# Hardware_v4.net
KiCad netlist of a schematic drawn in EAGLE
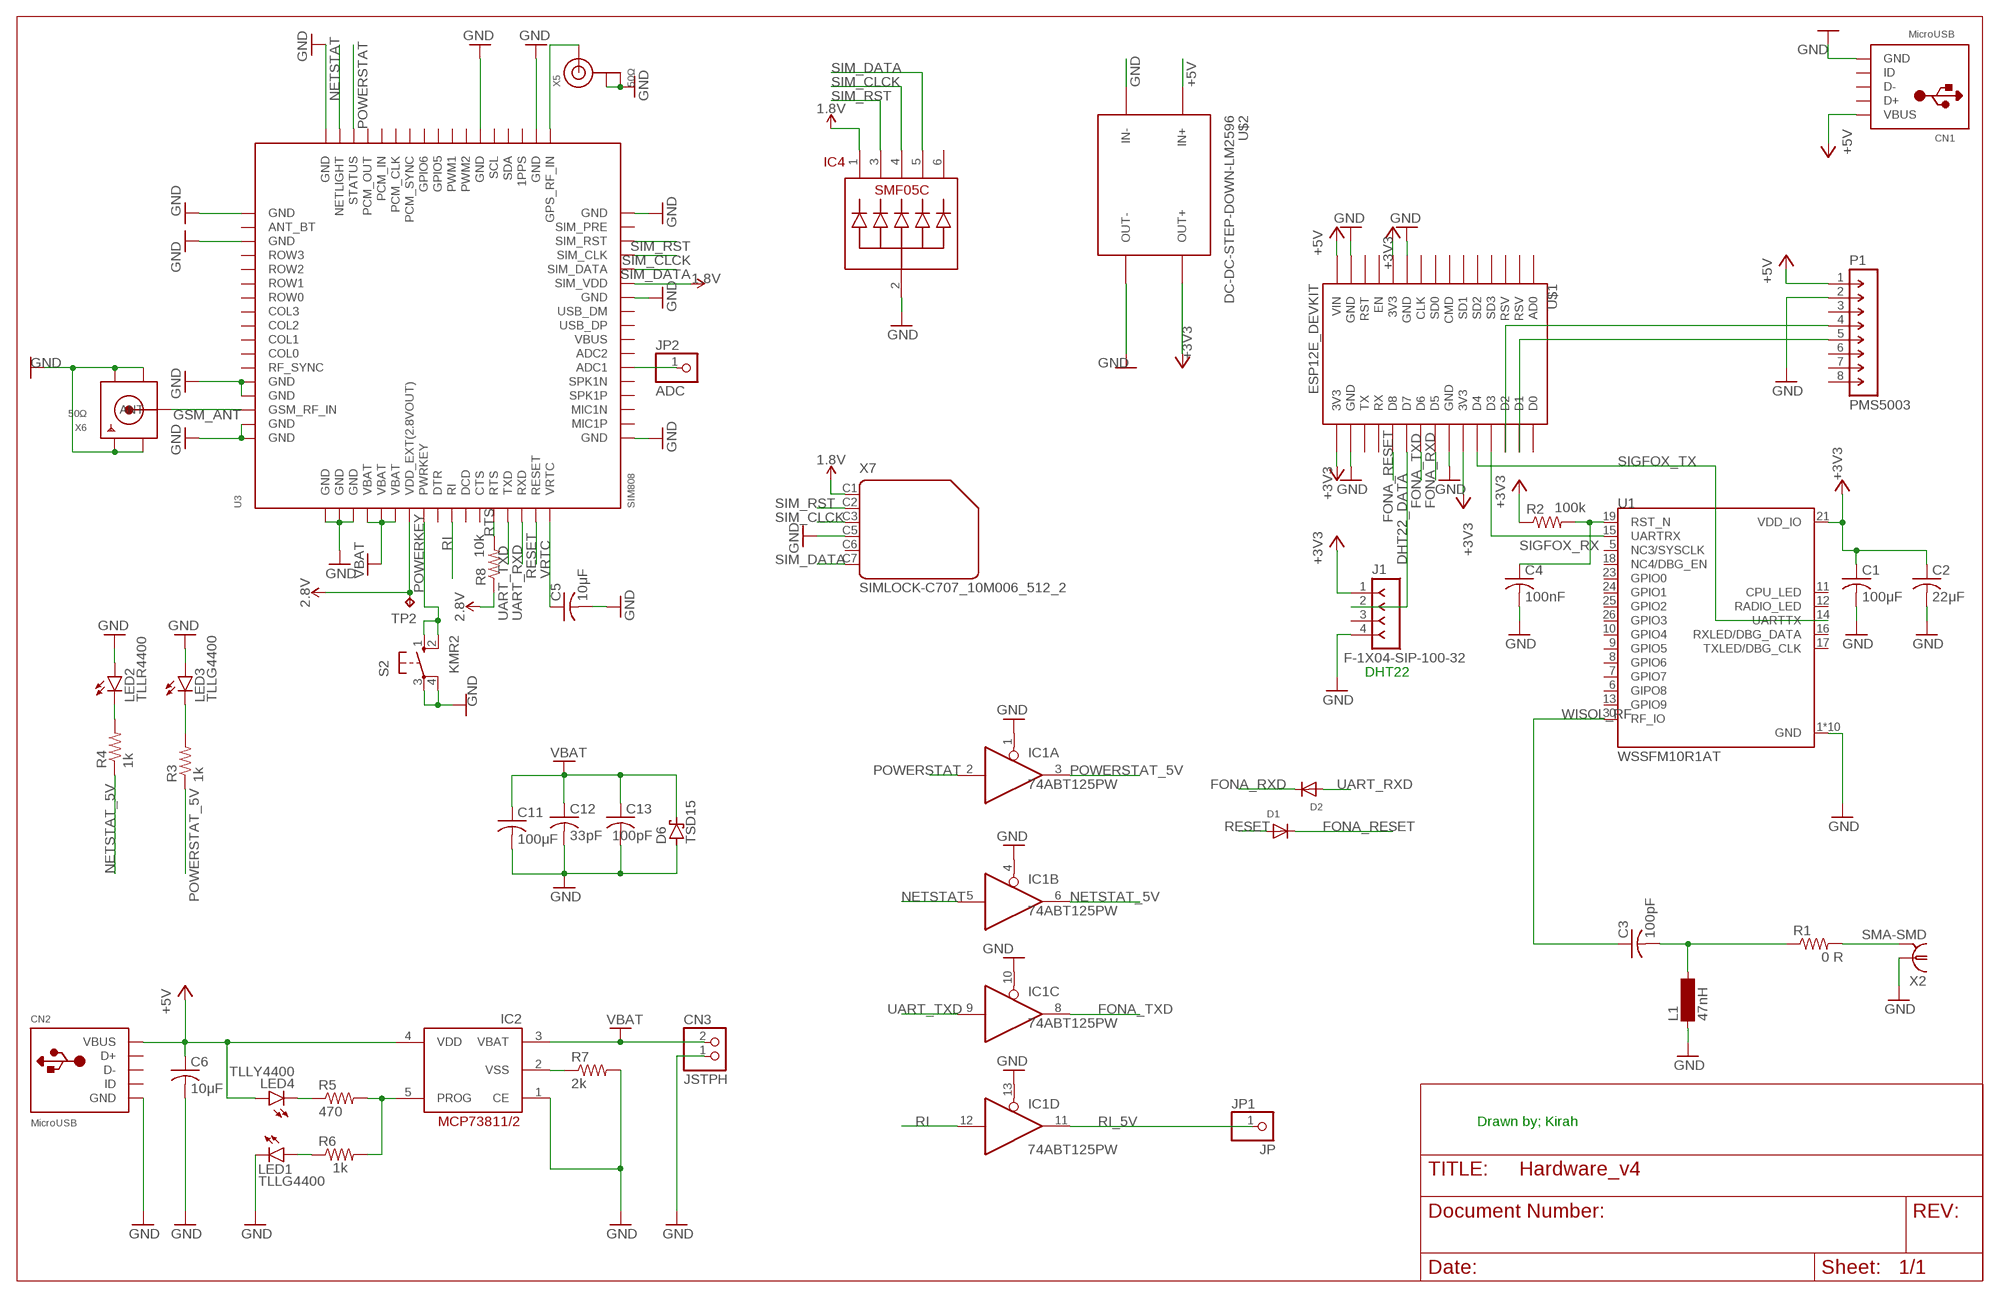
[diagram p0: schematic, sheet 1]

(export (version "E")
  (design (tool "Eeschema 10.0.6"))
  (components
    (comp (ref "C1")
      (value "100μF")
      (footprint "eagle-import:C0201")
      (libsource (lib "eagle-import") (part "rcl_334_C-USC0201"))
    )
    (comp (ref "C2")
      (value "22μF")
      (footprint "eagle-import:C0201")
      (libsource (lib "eagle-import") (part "rcl_334_C-USC0201"))
    )
    (comp (ref "C3")
      (value "100pF")
      (footprint "eagle-import:C0402K")
      (libsource (lib "eagle-import") (part "rcl_334_C-USC0402K"))
    )
    (comp (ref "C4")
      (value "100nF")
      (footprint "eagle-import:C0201")
      (libsource (lib "eagle-import") (part "rcl_334_C-USC0201"))
    )
    (comp (ref "C5")
      (value "10μF")
      (footprint "eagle-import:C0201")
      (libsource (lib "eagle-import") (part "rcl_334_C-USC0201"))
    )
    (comp (ref "C6")
      (value "10μF")
      (footprint "eagle-import:C0201")
      (libsource (lib "eagle-import") (part "rcl_334_C-USC0201"))
    )
    (comp (ref "C11")
      (value "100μF")
      (footprint "eagle-import:C0402")
      (libsource (lib "eagle-import") (part "C-USC0402"))
    )
    (comp (ref "C12")
      (value "33pF")
      (footprint "eagle-import:C0402")
      (libsource (lib "eagle-import") (part "C-USC0402"))
    )
    (comp (ref "C13")
      (value "100pF")
      (footprint "eagle-import:C0402")
      (libsource (lib "eagle-import") (part "C-USC0402"))
    )
    (comp (ref "CN1")
      (value "MicroUSB")
      (footprint "eagle-import:USB-MINIB")
      (libsource (lib "eagle-import") (part "USBMINIB"))
    )
    (comp (ref "CN2")
      (value "MicroUSB")
      (footprint "eagle-import:USB-MINIB")
      (libsource (lib "eagle-import") (part "adafruit@1_USBMINIB"))
    )
    (comp (ref "CN3")
      (value "JSTPH")
      (footprint "eagle-import:JST-PH-2-SMT")
      (libsource (lib "eagle-import") (part "JST_2PIN-SMT"))
    )
    (comp (ref "D1")
      (value "DIODESMA")
      (footprint "eagle-import:SMADIODE")
      (libsource (lib "eagle-import") (part "DIODESMA"))
    )
    (comp (ref "D2")
      (value "DIODESMA")
      (footprint "eagle-import:SMADIODE")
      (libsource (lib "eagle-import") (part "DIODESMA"))
    )
    (comp (ref "D6")
      (value "TSD15")
      (footprint "eagle-import:CB429-15")
      (libsource (lib "eagle-import") (part "TSD15"))
    )
    (comp (ref "IC1")
      (value "74ABT125PW")
      (footprint "eagle-import:TSSOP14")
      (libsource (lib "eagle-import") (part "74125PWABT"))
    )
    (comp (ref "IC2")
      (value "MCP73811/2")
      (footprint "eagle-import:SOT23-5L")
      (libsource (lib "eagle-import") (part "MCP73811/2"))
    )
    (comp (ref "IC4")
      (value "SMF05C")
      (footprint "eagle-import:SC-70-6")
      (libsource (lib "eagle-import") (part "SMF05C"))
    )
    (comp (ref "J1")
      (value "F-1X04-SIP-100-32")
      (footprint "eagle-import:SIP-100-04-32")
      (libsource (lib "eagle-import") (part "F-1X04-SIP-100-32"))
    )
    (comp (ref "JP1")
      (value "JP")
      (footprint "eagle-import:1X01-CLEANBIG")
      (libsource (lib "eagle-import") (part "PINHD-1X1CB"))
    )
    (comp (ref "JP2")
      (value "ADC")
      (footprint "eagle-import:1X01M")
      (libsource (lib "eagle-import") (part "PINHD-1X01_2.00"))
    )
    (comp (ref "L1")
      (value "47nH")
      (footprint "eagle-import:SM-1206")
      (libsource (lib "eagle-import") (part "SM-1206"))
    )
    (comp (ref "LED1")
      (value "TLLG4400")
      (footprint "eagle-import:LED3MM")
      (fields (field (name "MF") "VISHAY SEMICONDUCTOR"))
      (libsource (lib "eagle-import") (part "TLLG4400"))
    )
    (comp (ref "LED2")
      (value "TLLR4400")
      (footprint "eagle-import:LED3MM")
      (fields (field (name "MF") "VISHAY SEMICONDUCTOR"))
      (libsource (lib "eagle-import") (part "TLLR4400"))
    )
    (comp (ref "LED3")
      (value "TLLG4400")
      (footprint "eagle-import:LED3MM")
      (fields (field (name "MF") "VISHAY SEMICONDUCTOR"))
      (libsource (lib "eagle-import") (part "TLLG4400"))
    )
    (comp (ref "LED4")
      (value "TLLY4400")
      (footprint "eagle-import:LED3MM")
      (fields (field (name "MF") "VISHAY SEMICONDUCTOR"))
      (libsource (lib "eagle-import") (part "TLLY4400"))
    )
    (comp (ref "P1")
      (value "PMS5003")
      (footprint "eagle-import:SIP-100-08-40")
      (libsource (lib "eagle-import") (part "M-1X08-SIP-100-40"))
    )
    (comp (ref "R1")
      (value "0 R")
      (footprint "eagle-import:R01005")
      (libsource (lib "eagle-import") (part "R-US_01005"))
    )
    (comp (ref "R2")
      (value "100k")
      (footprint "eagle-import:R0201")
      (libsource (lib "eagle-import") (part "R-US_R0201"))
    )
    (comp (ref "R3")
      (value "1k")
      (footprint "eagle-import:R01005")
      (libsource (lib "eagle-import") (part "R-US_01005"))
    )
    (comp (ref "R4")
      (value "1k")
      (footprint "eagle-import:R01005")
      (libsource (lib "eagle-import") (part "R-US_01005"))
    )
    (comp (ref "R5")
      (value "470")
      (footprint "eagle-import:R01005")
      (libsource (lib "eagle-import") (part "R-US_01005"))
    )
    (comp (ref "R6")
      (value "1k")
      (footprint "eagle-import:R01005")
      (libsource (lib "eagle-import") (part "R-US_01005"))
    )
    (comp (ref "R7")
      (value "2k")
      (footprint "eagle-import:R01005")
      (libsource (lib "eagle-import") (part "R-US_01005"))
    )
    (comp (ref "R8")
      (value "10k")
      (footprint "eagle-import:R01005")
      (libsource (lib "eagle-import") (part "R-US_01005"))
    )
    (comp (ref "S2")
      (value "KMR2")
      (footprint "eagle-import:B3F_40XX")
      (libsource (lib "eagle-import") (part "40/XX"))
    )
    (comp (ref "TP2")
      (value "TPTP10R")
      (footprint "eagle-import:TP10R")
      (libsource (lib "eagle-import") (part "TPTP10R"))
    )
    (comp (ref "U$1")
      (value "ESP12E_DEVKIT")
      (footprint "eagle-import:ESP12E_DEVKIT")
      (libsource (lib "eagle-import") (part "ESP12E_DEVKIT"))
    )
    (comp (ref "U$2")
      (value "DC-DC-STEP-DOWN-LM2596")
      (footprint "eagle-import:DC-DC-STEP-DOWN-LM2596")
      (libsource (lib "eagle-import") (part "DC-DC-STEP-DOWN-LM2596"))
    )
    (comp (ref "U1")
      (value "WSSFM10R1AT")
      (footprint "eagle-import:XCVR_WSSFM10R1AT")
      (fields (field (name "MF") "Avnet Design Services"))
      (libsource (lib "eagle-import") (part "WSSFM10R1AT"))
    )
    (comp (ref "U3")
      (value "SIM808")
      (footprint "eagle-import:SIM900_SMT")
      (libsource (lib "eagle-import") (part "GSM_SIM808_LITERAL"))
    )
    (comp (ref "X2")
      (value "SMA-SMD")
      (footprint "eagle-import:SMA-SMD")
      (libsource (lib "eagle-import") (part "SMA-SMD"))
    )
    (comp (ref "X5")
      (value "50Ω")
      (footprint "eagle-import:U.FL")
      (libsource (lib "eagle-import") (part "ANTENNA_U.FL"))
    )
    (comp (ref "X6")
      (value "50Ω")
      (footprint "eagle-import:SMA_EDGELAUNCH_UFL")
      (libsource (lib "eagle-import") (part "SMACONNECTOR_EDGE_UFL"))
    )
    (comp (ref "X7")
      (value "SIMLOCK-C707_10M006_512_2")
      (footprint "eagle-import:C707_10M006_512_2")
      (libsource (lib "eagle-import") (part "SIMLOCK-C707_10M006_512_2"))
    )
  )
  (nets
    (net (code "1") (name "+3V3") (class "Default")
      (node (ref "C1") (pin "1") (pinfunction "1_1") (pintype "passive"))
      (node (ref "C2") (pin "1") (pinfunction "1_1") (pintype "passive"))
      (node (ref "J1") (pin "1") (pinfunction "1_1") (pintype "passive"))
      (node (ref "R2") (pin "1") (pinfunction "1_1") (pintype "passive"))
      (node (ref "U$1") (pin "3V3@0") (pinfunction "3V3_3V3@0") (pintype "bidirectional"))
      (node (ref "U$1") (pin "3V3@1") (pinfunction "3V3_3V3@1") (pintype "bidirectional"))
      (node (ref "U$1") (pin "3V3@2") (pinfunction "3V3_3V3@2") (pintype "bidirectional"))
      (node (ref "U$2") (pin "OUT+") (pinfunction "OUT+_OUT+") (pintype "bidirectional"))
      (node (ref "U1") (pin "21") (pinfunction "VDD_IO_21") (pintype "power_in"))
    )
    (net (code "2") (name "+5V") (class "Default")
      (node (ref "C6") (pin "1") (pinfunction "1_1") (pintype "passive"))
      (node (ref "CN1") (pin "VBUS") (pinfunction "VBUS_VBUS") (pintype "power_in"))
      (node (ref "CN2") (pin "VBUS") (pinfunction "VBUS_VBUS") (pintype "power_in"))
      (node (ref "IC2") (pin "4") (pinfunction "VDD_4") (pintype "power_in"))
      (node (ref "LED4") (pin "A") (pinfunction "A_A") (pintype "passive"))
      (node (ref "P1") (pin "1") (pinfunction "1_1") (pintype "passive"))
      (node (ref "U$1") (pin "VIN") (pinfunction "VIN_VIN") (pintype "bidirectional"))
      (node (ref "U$2") (pin "IN+") (pinfunction "IN+_IN+") (pintype "bidirectional"))
    )
    (net (code "3") (name "/DHT22_DATA") (class "Default")
      (node (ref "J1") (pin "2") (pinfunction "2_2") (pintype "passive"))
      (node (ref "U$1") (pin "D7") (pinfunction "D7_D7") (pintype "bidirectional"))
    )
    (net (code "4") (name "/FONA_RESET") (class "Default")
      (node (ref "D1") (pin "C") (pinfunction "C_C") (pintype "passive"))
      (node (ref "U$1") (pin "D8") (pinfunction "D8_D8") (pintype "bidirectional"))
    )
    (net (code "5") (name "/FONA_RXD") (class "Default")
      (node (ref "D2") (pin "C") (pinfunction "C_C") (pintype "passive"))
      (node (ref "U$1") (pin "D5") (pinfunction "D5_D5") (pintype "bidirectional"))
    )
    (net (code "6") (name "/FONA_TXD") (class "Default")
      (node (ref "IC1") (pin "8") (pinfunction "O_8") (pintype "tri_state"))
      (node (ref "U$1") (pin "D6") (pinfunction "D6_D6") (pintype "bidirectional"))
    )
    (net (code "7") (name "/GSM_ANT") (class "Default")
      (node (ref "U3") (pin "P$66") (pinfunction "GSM_RF_IN_P$66") (pintype "input"))
      (node (ref "X6") (pin "P") (pinfunction "ANT_P") (pintype "bidirectional"))
    )
    (net (code "8") (name "/NETSTAT") (class "Default")
      (node (ref "IC1") (pin "5") (pinfunction "I_5") (pintype "input"))
      (node (ref "U3") (pin "P$50") (pinfunction "NETLIGHT_P$50") (pintype "output"))
    )
    (net (code "9") (name "/NETSTAT_5V") (class "Default")
      (node (ref "IC1") (pin "6") (pinfunction "O_6") (pintype "tri_state"))
      (node (ref "R4") (pin "1") (pinfunction "1_1") (pintype "passive"))
    )
    (net (code "10") (name "/POWERKEY") (class "Default")
      (node (ref "S2") (pin "1") (pinfunction "S_1") (pintype "passive"))
      (node (ref "S2") (pin "2") (pinfunction "S1_2") (pintype "passive"))
      (node (ref "U3") (pin "P$8") (pinfunction "PWRKEY_P$8") (pintype "input"))
    )
    (net (code "11") (name "/POWERSTAT") (class "Default")
      (node (ref "IC1") (pin "2") (pinfunction "I_2") (pintype "input"))
      (node (ref "U3") (pin "P$49") (pinfunction "STATUS_P$49") (pintype "output"))
    )
    (net (code "12") (name "/POWERSTAT_5V") (class "Default")
      (node (ref "IC1") (pin "3") (pinfunction "O_3") (pintype "tri_state"))
      (node (ref "R3") (pin "1") (pinfunction "1_1") (pintype "passive"))
    )
    (net (code "13") (name "/RESET") (class "Default")
      (node (ref "D1") (pin "A") (pinfunction "A_A") (pintype "passive"))
      (node (ref "U3") (pin "P$16") (pinfunction "RESET_P$16") (pintype "input"))
    )
    (net (code "14") (name "/RI") (class "Default")
      (node (ref "IC1") (pin "12") (pinfunction "I_12") (pintype "input"))
      (node (ref "U3") (pin "P$10") (pinfunction "RI_P$10") (pintype "output"))
    )
    (net (code "15") (name "/RI_5V") (class "Default")
      (node (ref "IC1") (pin "11") (pinfunction "O_11") (pintype "tri_state"))
      (node (ref "JP1") (pin "1") (pinfunction "1_1") (pintype "passive"))
    )
    (net (code "16") (name "/RTS") (class "Default")
      (node (ref "R8") (pin "2") (pinfunction "2_2") (pintype "passive"))
      (node (ref "U3") (pin "P$13") (pinfunction "RTS_P$13") (pintype "input"))
    )
    (net (code "17") (name "/SIGFOX_RX") (class "Default")
      (node (ref "U$1") (pin "D3") (pinfunction "D3_D3") (pintype "bidirectional"))
      (node (ref "U1") (pin "15") (pinfunction "UARTRX_15") (pintype "input"))
    )
    (net (code "18") (name "/SIGFOX_TX") (class "Default")
      (node (ref "U$1") (pin "D4") (pinfunction "D4_D4") (pintype "bidirectional"))
      (node (ref "U1") (pin "14") (pinfunction "UARTTX_14") (pintype "output"))
    )
    (net (code "19") (name "/SIM_CLCK") (class "Default")
      (node (ref "IC4") (pin "4") (pinfunction "4_4") (pintype "bidirectional"))
      (node (ref "U3") (pin "P$31") (pinfunction "SIM_CLK_P$31") (pintype "output"))
      (node (ref "X7") (pin "C3") (pinfunction "3_C3") (pintype "passive"))
    )
    (net (code "20") (name "/SIM_DATA") (class "Default")
      (node (ref "IC4") (pin "5") (pinfunction "5_5") (pintype "bidirectional"))
      (node (ref "U3") (pin "P$30") (pinfunction "SIM_DATA_P$30") (pintype "bidirectional"))
      (node (ref "X7") (pin "C7") (pinfunction "6_C7") (pintype "passive"))
    )
    (net (code "21") (name "/SIM_RST") (class "Default")
      (node (ref "IC4") (pin "3") (pinfunction "3_3") (pintype "bidirectional"))
      (node (ref "U3") (pin "P$32") (pinfunction "SIM_RST_P$32") (pintype "output"))
      (node (ref "X7") (pin "C2") (pinfunction "2_C2") (pintype "passive"))
    )
    (net (code "22") (name "/UART_RXD") (class "Default")
      (node (ref "D2") (pin "A") (pinfunction "A_A") (pintype "passive"))
      (node (ref "U3") (pin "P$15") (pinfunction "RXD_P$15") (pintype "input"))
    )
    (net (code "23") (name "/UART_TXD") (class "Default")
      (node (ref "IC1") (pin "9") (pinfunction "I_9") (pintype "input"))
      (node (ref "U3") (pin "P$14") (pinfunction "TXD_P$14") (pintype "output"))
    )
    (net (code "24") (name "/VBUS") (class "Default")
      (node (ref "U3") (pin "P$25") (pinfunction "VBUS_P$25") (pintype "power_in"))
    )
    (net (code "25") (name "/VRTC") (class "Default")
      (node (ref "C5") (pin "1") (pinfunction "1_1") (pintype "passive"))
      (node (ref "U3") (pin "P$17") (pinfunction "VRTC_P$17") (pintype "power_in"))
    )
    (net (code "26") (name "/WISOL_RF") (class "Default")
      (node (ref "C3") (pin "1") (pinfunction "1_1") (pintype "passive"))
      (node (ref "U1") (pin "30") (pinfunction "RF_IO_30") (pintype "bidirectional"))
    )
    (net (code "27") (name "1.8V") (class "Default")
      (node (ref "IC4") (pin "1") (pinfunction "1_1") (pintype "bidirectional"))
      (node (ref "U3") (pin "P$29") (pinfunction "SIM_VDD_P$29") (pintype "power_in"))
      (node (ref "X7") (pin "C1") (pinfunction "1_C1") (pintype "passive"))
    )
    (net (code "28") (name "2.8V") (class "Default")
      (node (ref "R8") (pin "1") (pinfunction "1_1") (pintype "passive"))
      (node (ref "TP2") (pin "TP") (pinfunction "TP_TP") (pintype "input"))
      (node (ref "U3") (pin "P$7") (pinfunction "VDD_EXT(2.8VOUT)_P$7") (pintype "power_in"))
    )
    (net (code "29") (name "GND") (class "Default")
      (node (ref "C1") (pin "2") (pinfunction "2_2") (pintype "passive"))
      (node (ref "C11") (pin "2") (pinfunction "2_2") (pintype "passive"))
      (node (ref "C12") (pin "2") (pinfunction "2_2") (pintype "passive"))
      (node (ref "C13") (pin "2") (pinfunction "2_2") (pintype "passive"))
      (node (ref "C2") (pin "2") (pinfunction "2_2") (pintype "passive"))
      (node (ref "C4") (pin "2") (pinfunction "2_2") (pintype "passive"))
      (node (ref "C5") (pin "2") (pinfunction "2_2") (pintype "passive"))
      (node (ref "C6") (pin "2") (pinfunction "2_2") (pintype "passive"))
      (node (ref "CN1") (pin "GND") (pinfunction "GND_GND") (pintype "power_in"))
      (node (ref "CN2") (pin "GND") (pinfunction "GND_GND") (pintype "power_in"))
      (node (ref "CN3") (pin "1") (pinfunction "2_1") (pintype "passive"))
      (node (ref "D6") (pin "A") (pinfunction "A_A") (pintype "passive"))
      (node (ref "IC1") (pin "1") (pinfunction "OE_1") (pintype "input"))
      (node (ref "IC1") (pin "10") (pinfunction "OE_10") (pintype "input"))
      (node (ref "IC1") (pin "13") (pinfunction "OE_13") (pintype "input"))
      (node (ref "IC1") (pin "4") (pinfunction "OE_4") (pintype "input"))
      (node (ref "IC2") (pin "1") (pinfunction "CE_1") (pintype "input"))
      (node (ref "IC4") (pin "2") (pinfunction "2_2") (pintype "bidirectional"))
      (node (ref "J1") (pin "4") (pinfunction "4_4") (pintype "passive"))
      (node (ref "L1") (pin "1") (pinfunction "1_1") (pintype "passive"))
      (node (ref "LED1") (pin "K") (pinfunction "C_K") (pintype "passive"))
      (node (ref "LED2") (pin "A") (pinfunction "A_A") (pintype "passive"))
      (node (ref "LED3") (pin "A") (pinfunction "A_A") (pintype "passive"))
      (node (ref "P1") (pin "2") (pinfunction "2_2") (pintype "passive"))
      (node (ref "R7") (pin "2") (pinfunction "2_2") (pintype "passive"))
      (node (ref "S2") (pin "3") (pinfunction "P_3") (pintype "passive"))
      (node (ref "S2") (pin "4") (pinfunction "P1_4") (pintype "passive"))
      (node (ref "U$1") (pin "GND@0") (pinfunction "GND_GND@0") (pintype "bidirectional"))
      (node (ref "U$1") (pin "GND@1") (pinfunction "GND_GND@1") (pintype "bidirectional"))
      (node (ref "U$1") (pin "GND@2") (pinfunction "GND_GND@2") (pintype "bidirectional"))
      (node (ref "U$1") (pin "GND@3") (pinfunction "GND_GND@3") (pintype "bidirectional"))
      (node (ref "U$2") (pin "IN-") (pinfunction "IN-_IN-") (pintype "bidirectional"))
      (node (ref "U$2") (pin "OUT-") (pinfunction "OUT-_OUT-") (pintype "bidirectional"))
      (node (ref "U1") (pin "1") (pinfunction "GND_1") (pintype "power_in"))
      (node (ref "U1") (pin "2") (pinfunction "GND_2") (pintype "power_in"))
      (node (ref "U1") (pin "20") (pinfunction "GND_20") (pintype "power_in"))
      (node (ref "U1") (pin "22") (pinfunction "GND_22") (pintype "power_in"))
      (node (ref "U1") (pin "27") (pinfunction "GND_27") (pintype "power_in"))
      (node (ref "U1") (pin "28") (pinfunction "GND_28") (pintype "power_in"))
      (node (ref "U1") (pin "29") (pinfunction "GND_29") (pintype "power_in"))
      (node (ref "U1") (pin "3") (pinfunction "GND_3") (pintype "power_in"))
      (node (ref "U1") (pin "31") (pinfunction "GND_31") (pintype "power_in"))
      (node (ref "U1") (pin "4") (pinfunction "GND_4") (pintype "power_in"))
      (node (ref "U3") (pin "P$1") (pinfunction "GND_P$1") (pintype "power_in"))
      (node (ref "U3") (pin "P$18") (pinfunction "GND_P$18") (pintype "power_in"))
      (node (ref "U3") (pin "P$2") (pinfunction "GND_P$2") (pintype "power_in"))
      (node (ref "U3") (pin "P$28") (pinfunction "GND_P$28") (pintype "power_in"))
      (node (ref "U3") (pin "P$3") (pinfunction "GND_P$3") (pintype "power_in"))
      (node (ref "U3") (pin "P$34") (pinfunction "GND_P$34") (pintype "power_in"))
      (node (ref "U3") (pin "P$36") (pinfunction "GND_P$36") (pintype "power_in"))
      (node (ref "U3") (pin "P$40") (pinfunction "GND_P$40") (pintype "power_in"))
      (node (ref "U3") (pin "P$51") (pinfunction "GND_P$51") (pintype "power_in"))
      (node (ref "U3") (pin "P$52") (pinfunction "GND_P$52") (pintype "power_in"))
      (node (ref "U3") (pin "P$54") (pinfunction "GND_P$54") (pintype "power_in"))
      (node (ref "U3") (pin "P$64") (pinfunction "GND_P$64") (pintype "power_in"))
      (node (ref "U3") (pin "P$65") (pinfunction "GND_P$65") (pintype "power_in"))
      (node (ref "U3") (pin "P$67") (pinfunction "GND_P$67") (pintype "power_in"))
      (node (ref "U3") (pin "P$68") (pinfunction "GND_P$68") (pintype "power_in"))
      (node (ref "X2") (pin "1") (pinfunction "1_1") (pintype "passive"))
      (node (ref "X5") (pin "1") (pinfunction "GND_1") (pintype "passive"))
      (node (ref "X5") (pin "2") (pinfunction "GND_2") (pintype "passive"))
      (node (ref "X6") (pin "GND@1") (pinfunction "GND1_GND@1") (pintype "power_in"))
      (node (ref "X6") (pin "GND@2") (pinfunction "GND2_GND@2") (pintype "power_in"))
      (node (ref "X6") (pin "GND@3") (pinfunction "GND3_GND@3") (pintype "power_in"))
      (node (ref "X6") (pin "GND@4") (pinfunction "GND4_GND@4") (pintype "power_in"))
      (node (ref "X7") (pin "C5") (pinfunction "4_C5") (pintype "passive"))
    )
    (net (code "30") (name "Net-(C3-Pad2)") (class "Default")
      (node (ref "C3") (pin "2") (pinfunction "2_2") (pintype "passive"))
      (node (ref "L1") (pin "2") (pinfunction "2_2") (pintype "passive"))
      (node (ref "R1") (pin "1") (pinfunction "1_1") (pintype "passive"))
    )
    (net (code "31") (name "Net-(IC2-PROG)") (class "Default")
      (node (ref "IC2") (pin "5") (pinfunction "PROG_5") (pintype "input"))
      (node (ref "R5") (pin "2") (pinfunction "2_2") (pintype "passive"))
      (node (ref "R6") (pin "2") (pinfunction "2_2") (pintype "passive"))
    )
    (net (code "32") (name "Net-(IC2-VSS)") (class "Default")
      (node (ref "IC2") (pin "2") (pinfunction "VSS_2") (pintype "power_in"))
      (node (ref "R7") (pin "1") (pinfunction "1_1") (pintype "passive"))
    )
    (net (code "33") (name "Net-(LED1-PadA)") (class "Default")
      (node (ref "LED1") (pin "A") (pinfunction "A_A") (pintype "passive"))
      (node (ref "R6") (pin "1") (pinfunction "1_1") (pintype "passive"))
    )
    (net (code "34") (name "Net-(LED2-C)") (class "Default")
      (node (ref "LED2") (pin "K") (pinfunction "C_K") (pintype "passive"))
      (node (ref "R4") (pin "2") (pinfunction "2_2") (pintype "passive"))
    )
    (net (code "35") (name "Net-(LED3-C)") (class "Default")
      (node (ref "LED3") (pin "K") (pinfunction "C_K") (pintype "passive"))
      (node (ref "R3") (pin "2") (pinfunction "2_2") (pintype "passive"))
    )
    (net (code "36") (name "Net-(LED4-C)") (class "Default")
      (node (ref "LED4") (pin "K") (pinfunction "C_K") (pintype "passive"))
      (node (ref "R5") (pin "1") (pinfunction "1_1") (pintype "passive"))
    )
    (net (code "37") (name "Net-(P1-Pad4)") (class "Default")
      (node (ref "P1") (pin "4") (pinfunction "4_4") (pintype "passive"))
      (node (ref "U$1") (pin "D2") (pinfunction "D2_D2") (pintype "bidirectional"))
    )
    (net (code "38") (name "Net-(P1-Pad5)") (class "Default")
      (node (ref "P1") (pin "5") (pinfunction "5_5") (pintype "passive"))
      (node (ref "U$1") (pin "D1") (pinfunction "D1_D1") (pintype "bidirectional"))
    )
    (net (code "39") (name "Net-(R1-Pad2)") (class "Default")
      (node (ref "R1") (pin "2") (pinfunction "2_2") (pintype "passive"))
      (node (ref "X2") (pin "2@1") (pinfunction "2_2@1") (pintype "passive"))
      (node (ref "X2") (pin "2@2") (pinfunction "2_2@2") (pintype "passive"))
      (node (ref "X2") (pin "2@3") (pinfunction "2_2@3") (pintype "passive"))
      (node (ref "X2") (pin "2@4") (pinfunction "2_2@4") (pintype "passive"))
      (node (ref "X2") (pin "2@5") (pinfunction "2_2@5") (pintype "passive"))
      (node (ref "X2") (pin "2@6") (pinfunction "2_2@6") (pintype "passive"))
    )
    (net (code "40") (name "Net-(U1-RST_N)") (class "Default")
      (node (ref "C4") (pin "1") (pinfunction "1_1") (pintype "passive"))
      (node (ref "R2") (pin "2") (pinfunction "2_2") (pintype "passive"))
      (node (ref "U1") (pin "19") (pinfunction "RST_N_19") (pintype "input"))
    )
    (net (code "41") (name "Net-(U3-ADC1)") (class "Default")
      (node (ref "JP2") (pin "1") (pinfunction "1_1") (pintype "passive"))
      (node (ref "U3") (pin "P$23") (pinfunction "ADC1_P$23") (pintype "input"))
    )
    (net (code "42") (name "Net-(U3-GPS_RF_IN)") (class "Default")
      (node (ref "U3") (pin "P$35") (pinfunction "GPS_RF_IN_P$35") (pintype "bidirectional"))
      (node (ref "X5") (pin "3") (pinfunction "SIGNAL_3") (pintype "passive"))
    )
    (net (code "43") (name "VBAT") (class "Default")
      (node (ref "C11") (pin "1") (pinfunction "1_1") (pintype "passive"))
      (node (ref "C12") (pin "1") (pinfunction "1_1") (pintype "passive"))
      (node (ref "C13") (pin "1") (pinfunction "1_1") (pintype "passive"))
      (node (ref "CN3") (pin "2") (pinfunction "1_2") (pintype "passive"))
      (node (ref "D6") (pin "C") (pinfunction "C_C") (pintype "passive"))
      (node (ref "IC2") (pin "3") (pinfunction "VBAT_3") (pintype "bidirectional"))
      (node (ref "U3") (pin "P$4") (pinfunction "VBAT_P$4") (pintype "power_in"))
      (node (ref "U3") (pin "P$5") (pinfunction "VBAT_P$5") (pintype "power_in"))
      (node (ref "U3") (pin "P$6") (pinfunction "VBAT_P$6") (pintype "power_in"))
    )
    (net (code "44") (name "unconnected-(CN1-PadD+)") (class "Default")
      (node (ref "CN1") (pin "D+") (pinfunction "D+_D+") (pintype "bidirectional"))
    )
    (net (code "45") (name "unconnected-(CN1-PadD-)") (class "Default")
      (node (ref "CN1") (pin "D-") (pinfunction "D-_D-") (pintype "bidirectional"))
    )
    (net (code "46") (name "unconnected-(CN1-PadID)") (class "Default")
      (node (ref "CN1") (pin "ID") (pinfunction "ID_ID") (pintype "bidirectional"))
    )
    (net (code "47") (name "unconnected-(CN2-PadD+)") (class "Default")
      (node (ref "CN2") (pin "D+") (pinfunction "D+_D+") (pintype "bidirectional"))
    )
    (net (code "48") (name "unconnected-(CN2-PadD-)") (class "Default")
      (node (ref "CN2") (pin "D-") (pinfunction "D-_D-") (pintype "bidirectional"))
    )
    (net (code "49") (name "unconnected-(CN2-PadID)") (class "Default")
      (node (ref "CN2") (pin "ID") (pinfunction "ID_ID") (pintype "bidirectional"))
    )
    (net (code "50") (name "unconnected-(IC4-Pad6)") (class "Default")
      (node (ref "IC4") (pin "6") (pinfunction "6_6") (pintype "bidirectional"))
    )
    (net (code "51") (name "unconnected-(J1-Pad3)") (class "Default")
      (node (ref "J1") (pin "3") (pinfunction "3_3") (pintype "passive"))
    )
    (net (code "52") (name "unconnected-(P1-Pad3)") (class "Default")
      (node (ref "P1") (pin "3") (pinfunction "3_3") (pintype "passive"))
    )
    (net (code "53") (name "unconnected-(P1-Pad6)") (class "Default")
      (node (ref "P1") (pin "6") (pinfunction "6_6") (pintype "passive"))
    )
    (net (code "54") (name "unconnected-(P1-Pad7)") (class "Default")
      (node (ref "P1") (pin "7") (pinfunction "7_7") (pintype "passive"))
    )
    (net (code "55") (name "unconnected-(P1-Pad8)") (class "Default")
      (node (ref "P1") (pin "8") (pinfunction "8_8") (pintype "passive"))
    )
    (net (code "56") (name "unconnected-(U$1-PadAD0)") (class "Default")
      (node (ref "U$1") (pin "AD0") (pinfunction "AD0_AD0") (pintype "bidirectional"))
    )
    (net (code "57") (name "unconnected-(U$1-PadCLK)") (class "Default")
      (node (ref "U$1") (pin "CLK") (pinfunction "CLK_CLK") (pintype "bidirectional"))
    )
    (net (code "58") (name "unconnected-(U$1-PadCMD)") (class "Default")
      (node (ref "U$1") (pin "CMD") (pinfunction "CMD_CMD") (pintype "bidirectional"))
    )
    (net (code "59") (name "unconnected-(U$1-PadD0)") (class "Default")
      (node (ref "U$1") (pin "D0") (pinfunction "D0_D0") (pintype "bidirectional"))
    )
    (net (code "60") (name "unconnected-(U$1-PadEN)") (class "Default")
      (node (ref "U$1") (pin "EN") (pinfunction "EN_EN") (pintype "bidirectional"))
    )
    (net (code "61") (name "unconnected-(U$1-PadRST)") (class "Default")
      (node (ref "U$1") (pin "RST") (pinfunction "RST_RST") (pintype "bidirectional"))
    )
    (net (code "62") (name "unconnected-(U$1-PadRX)") (class "Default")
      (node (ref "U$1") (pin "RX") (pinfunction "RX_RX") (pintype "bidirectional"))
    )
    (net (code "63") (name "unconnected-(U$1-PadSD0)") (class "Default")
      (node (ref "U$1") (pin "SD0") (pinfunction "SD0_SD0") (pintype "bidirectional"))
    )
    (net (code "64") (name "unconnected-(U$1-PadSD1)") (class "Default")
      (node (ref "U$1") (pin "SD1") (pinfunction "SD1_SD1") (pintype "bidirectional"))
    )
    (net (code "65") (name "unconnected-(U$1-PadSD2)") (class "Default")
      (node (ref "U$1") (pin "SD2") (pinfunction "SD2_SD2") (pintype "bidirectional"))
    )
    (net (code "66") (name "unconnected-(U$1-PadSD3)") (class "Default")
      (node (ref "U$1") (pin "SD3") (pinfunction "SD3_SD3") (pintype "bidirectional"))
    )
    (net (code "67") (name "unconnected-(U$1-PadTX)") (class "Default")
      (node (ref "U$1") (pin "TX") (pinfunction "TX_TX") (pintype "bidirectional"))
    )
    (net (code "68") (name "unconnected-(U$1-RSV-PadRSV@0)") (class "Default")
      (node (ref "U$1") (pin "RSV@0") (pinfunction "RSV_RSV@0") (pintype "bidirectional"))
    )
    (net (code "69") (name "unconnected-(U$1-RSV-PadRSV@1)") (class "Default")
      (node (ref "U$1") (pin "RSV@1") (pinfunction "RSV_RSV@1") (pintype "bidirectional"))
    )
    (net (code "70") (name "unconnected-(U1-CPU_LED-Pad11)") (class "Default")
      (node (ref "U1") (pin "11") (pinfunction "CPU_LED_11") (pintype "output"))
    )
    (net (code "71") (name "unconnected-(U1-GIPO8-Pad6)") (class "Default")
      (node (ref "U1") (pin "6") (pinfunction "GIPO8_6") (pintype "bidirectional"))
    )
    (net (code "72") (name "unconnected-(U1-GPIO0-Pad23)") (class "Default")
      (node (ref "U1") (pin "23") (pinfunction "GPIO0_23") (pintype "bidirectional"))
    )
    (net (code "73") (name "unconnected-(U1-GPIO1-Pad24)") (class "Default")
      (node (ref "U1") (pin "24") (pinfunction "GPIO1_24") (pintype "bidirectional"))
    )
    (net (code "74") (name "unconnected-(U1-GPIO2-Pad25)") (class "Default")
      (node (ref "U1") (pin "25") (pinfunction "GPIO2_25") (pintype "bidirectional"))
    )
    (net (code "75") (name "unconnected-(U1-GPIO3-Pad26)") (class "Default")
      (node (ref "U1") (pin "26") (pinfunction "GPIO3_26") (pintype "bidirectional"))
    )
    (net (code "76") (name "unconnected-(U1-GPIO4-Pad10)") (class "Default")
      (node (ref "U1") (pin "10") (pinfunction "GPIO4_10") (pintype "input"))
    )
    (net (code "77") (name "unconnected-(U1-GPIO5-Pad9)") (class "Default")
      (node (ref "U1") (pin "9") (pinfunction "GPIO5_9") (pintype "bidirectional"))
    )
    (net (code "78") (name "unconnected-(U1-GPIO6-Pad8)") (class "Default")
      (node (ref "U1") (pin "8") (pinfunction "GPIO6_8") (pintype "bidirectional"))
    )
    (net (code "79") (name "unconnected-(U1-GPIO7-Pad7)") (class "Default")
      (node (ref "U1") (pin "7") (pinfunction "GPIO7_7") (pintype "bidirectional"))
    )
    (net (code "80") (name "unconnected-(U1-GPIO9-Pad13)") (class "Default")
      (node (ref "U1") (pin "13") (pinfunction "GPIO9_13") (pintype "input"))
    )
    (net (code "81") (name "unconnected-(U1-NC3{slash}SYSCLK-Pad5)") (class "Default")
      (node (ref "U1") (pin "5") (pinfunction "NC3/SYSCLK_5") (pintype "input"))
    )
    (net (code "82") (name "unconnected-(U1-NC4{slash}DBG_EN-Pad18)") (class "Default")
      (node (ref "U1") (pin "18") (pinfunction "NC4/DBG_EN_18") (pintype "input"))
    )
    (net (code "83") (name "unconnected-(U1-RADIO_LED-Pad12)") (class "Default")
      (node (ref "U1") (pin "12") (pinfunction "RADIO_LED_12") (pintype "output"))
    )
    (net (code "84") (name "unconnected-(U1-RXLED{slash}DBG_DATA-Pad16)") (class "Default")
      (node (ref "U1") (pin "16") (pinfunction "RXLED/DBG_DATA_16") (pintype "output"))
    )
    (net (code "85") (name "unconnected-(U1-TXLED{slash}DBG_CLK-Pad17)") (class "Default")
      (node (ref "U1") (pin "17") (pinfunction "TXLED/DBG_CLK_17") (pintype "output"))
    )
    (net (code "86") (name "unconnected-(U3-1PPS-PadP$37)") (class "Default")
      (node (ref "U3") (pin "P$37") (pinfunction "1PPS_P$37") (pintype "input"))
    )
    (net (code "87") (name "unconnected-(U3-ADC2-PadP$24)") (class "Default")
      (node (ref "U3") (pin "P$24") (pinfunction "ADC2_P$24") (pintype "input"))
    )
    (net (code "88") (name "unconnected-(U3-ANT_BT-PadP$53)") (class "Default")
      (node (ref "U3") (pin "P$53") (pinfunction "ANT_BT_P$53") (pintype "bidirectional"))
    )
    (net (code "89") (name "unconnected-(U3-COL0-PadP$62)") (class "Default")
      (node (ref "U3") (pin "P$62") (pinfunction "COL0_P$62") (pintype "input"))
    )
    (net (code "90") (name "unconnected-(U3-COL1-PadP$61)") (class "Default")
      (node (ref "U3") (pin "P$61") (pinfunction "COL1_P$61") (pintype "input"))
    )
    (net (code "91") (name "unconnected-(U3-COL2-PadP$60)") (class "Default")
      (node (ref "U3") (pin "P$60") (pinfunction "COL2_P$60") (pintype "input"))
    )
    (net (code "92") (name "unconnected-(U3-COL3-PadP$59)") (class "Default")
      (node (ref "U3") (pin "P$59") (pinfunction "COL3_P$59") (pintype "input"))
    )
    (net (code "93") (name "unconnected-(U3-CTS-PadP$12)") (class "Default")
      (node (ref "U3") (pin "P$12") (pinfunction "CTS_P$12") (pintype "output"))
    )
    (net (code "94") (name "unconnected-(U3-DCD-PadP$11)") (class "Default")
      (node (ref "U3") (pin "P$11") (pinfunction "DCD_P$11") (pintype "output"))
    )
    (net (code "95") (name "unconnected-(U3-DTR-PadP$9)") (class "Default")
      (node (ref "U3") (pin "P$9") (pinfunction "DTR_P$9") (pintype "input"))
    )
    (net (code "96") (name "unconnected-(U3-GPIO5-PadP$43)") (class "Default")
      (node (ref "U3") (pin "P$43") (pinfunction "GPIO5_P$43") (pintype "bidirectional"))
    )
    (net (code "97") (name "unconnected-(U3-GPIO6-PadP$44)") (class "Default")
      (node (ref "U3") (pin "P$44") (pinfunction "GPIO6_P$44") (pintype "bidirectional"))
    )
    (net (code "98") (name "unconnected-(U3-MIC1N-PadP$20)") (class "Default")
      (node (ref "U3") (pin "P$20") (pinfunction "MIC1N_P$20") (pintype "input"))
    )
    (net (code "99") (name "unconnected-(U3-MIC1P-PadP$19)") (class "Default")
      (node (ref "U3") (pin "P$19") (pinfunction "MIC1P_P$19") (pintype "input"))
    )
    (net (code "100") (name "unconnected-(U3-PCM_CLK-PadP$46)") (class "Default")
      (node (ref "U3") (pin "P$46") (pinfunction "PCM_CLK_P$46") (pintype "input"))
    )
    (net (code "101") (name "unconnected-(U3-PCM_IN-PadP$47)") (class "Default")
      (node (ref "U3") (pin "P$47") (pinfunction "PCM_IN_P$47") (pintype "input"))
    )
    (net (code "102") (name "unconnected-(U3-PCM_OUT-PadP$48)") (class "Default")
      (node (ref "U3") (pin "P$48") (pinfunction "PCM_OUT_P$48") (pintype "output"))
    )
    (net (code "103") (name "unconnected-(U3-PCM_SYNC-PadP$45)") (class "Default")
      (node (ref "U3") (pin "P$45") (pinfunction "PCM_SYNC_P$45") (pintype "output"))
    )
    (net (code "104") (name "unconnected-(U3-PWM1-PadP$42)") (class "Default")
      (node (ref "U3") (pin "P$42") (pinfunction "PWM1_P$42") (pintype "output"))
    )
    (net (code "105") (name "unconnected-(U3-PWM2-PadP$41)") (class "Default")
      (node (ref "U3") (pin "P$41") (pinfunction "PWM2_P$41") (pintype "output"))
    )
    (net (code "106") (name "unconnected-(U3-RF_SYNC-PadP$63)") (class "Default")
      (node (ref "U3") (pin "P$63") (pinfunction "RF_SYNC_P$63") (pintype "output"))
    )
    (net (code "107") (name "unconnected-(U3-ROW0-PadP$58)") (class "Default")
      (node (ref "U3") (pin "P$58") (pinfunction "ROW0_P$58") (pintype "output"))
    )
    (net (code "108") (name "unconnected-(U3-ROW1-PadP$57)") (class "Default")
      (node (ref "U3") (pin "P$57") (pinfunction "ROW1_P$57") (pintype "output"))
    )
    (net (code "109") (name "unconnected-(U3-ROW2-PadP$56)") (class "Default")
      (node (ref "U3") (pin "P$56") (pinfunction "ROW2_P$56") (pintype "output"))
    )
    (net (code "110") (name "unconnected-(U3-ROW3-PadP$55)") (class "Default")
      (node (ref "U3") (pin "P$55") (pinfunction "ROW3_P$55") (pintype "output"))
    )
    (net (code "111") (name "unconnected-(U3-SCL-PadP$39)") (class "Default")
      (node (ref "U3") (pin "P$39") (pinfunction "SCL_P$39") (pintype "output"))
    )
    (net (code "112") (name "unconnected-(U3-SDA-PadP$38)") (class "Default")
      (node (ref "U3") (pin "P$38") (pinfunction "SDA_P$38") (pintype "bidirectional"))
    )
    (net (code "113") (name "unconnected-(U3-SIM_PRE-PadP$33)") (class "Default")
      (node (ref "U3") (pin "P$33") (pinfunction "SIM_PRE_P$33") (pintype "input"))
    )
    (net (code "114") (name "unconnected-(U3-SPK1N-PadP$22)") (class "Default")
      (node (ref "U3") (pin "P$22") (pinfunction "SPK1N_P$22") (pintype "output"))
    )
    (net (code "115") (name "unconnected-(U3-SPK1P-PadP$21)") (class "Default")
      (node (ref "U3") (pin "P$21") (pinfunction "SPK1P_P$21") (pintype "output"))
    )
    (net (code "116") (name "unconnected-(U3-USB_DM-PadP$27)") (class "Default")
      (node (ref "U3") (pin "P$27") (pinfunction "USB_DM_P$27") (pintype "bidirectional"))
    )
    (net (code "117") (name "unconnected-(U3-USB_DP-PadP$26)") (class "Default")
      (node (ref "U3") (pin "P$26") (pinfunction "USB_DP_P$26") (pintype "bidirectional"))
    )
    (net (code "118") (name "unconnected-(X7-5-PadC6)") (class "Default")
      (node (ref "X7") (pin "C6") (pinfunction "5_C6") (pintype "passive"))
    )
  )
)
